# xmega-128a4u-switch.net
KiCad netlist of a schematic drawn in EAGLE
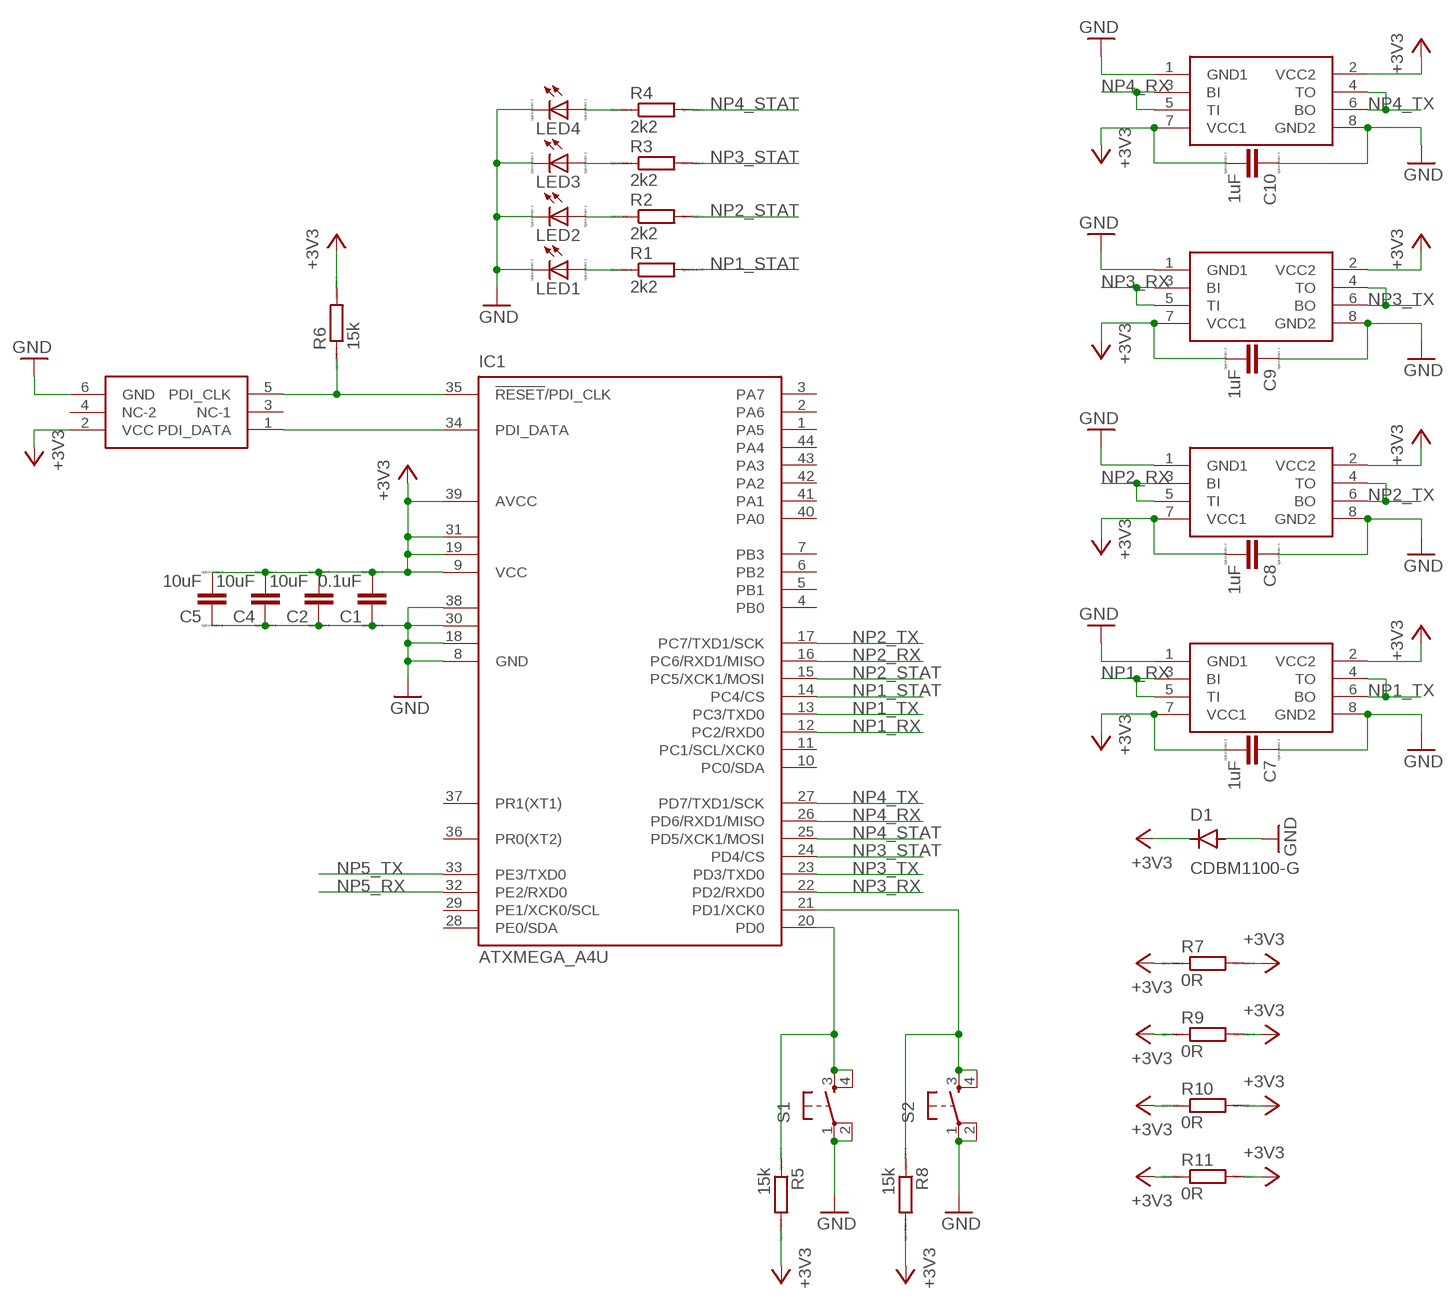
[diagram p0: schematic, sheet 1]

(export (version "E")
  (design (tool "Eeschema 10.0.6"))
  (components
    (comp (ref "C1")
      (value "0.1uF")
      (footprint "eagle-import:C0805")
      (libsource (lib "eagle-import") (part "C"))
    )
    (comp (ref "C2")
      (value "10uF")
      (footprint "eagle-import:C1206")
      (libsource (lib "eagle-import") (part "CC1206"))
    )
    (comp (ref "C4")
      (value "10uF")
      (footprint "eagle-import:C1206")
      (libsource (lib "eagle-import") (part "CC1206"))
    )
    (comp (ref "C5")
      (value "10uF")
      (footprint "eagle-import:C1206")
      (libsource (lib "eagle-import") (part "CC1206"))
    )
    (comp (ref "C7")
      (value "1uF")
      (footprint "eagle-import:C0805")
      (libsource (lib "eagle-import") (part "C"))
    )
    (comp (ref "C8")
      (value "1uF")
      (footprint "eagle-import:C0805")
      (libsource (lib "eagle-import") (part "C"))
    )
    (comp (ref "C9")
      (value "1uF")
      (footprint "eagle-import:C0805")
      (libsource (lib "eagle-import") (part "C"))
    )
    (comp (ref "C10")
      (value "1uF")
      (footprint "eagle-import:C0805")
      (libsource (lib "eagle-import") (part "C"))
    )
    (comp (ref "D1")
      (value "CDBM1100-G")
      (footprint "eagle-import:MINI-SMA")
      (libsource (lib "eagle-import") (part "CDBM1100-G"))
    )
    (comp (ref "IC1")
      (value "ATXMEGA_A4U")
      (footprint "eagle-import:TQFP44-13THIN")
      (libsource (lib "eagle-import") (part "ATXMEGA_A4U"))
    )
    (comp (ref "LED1")
      (value "LED_E")
      (footprint "eagle-import:LED_1206")
      (libsource (lib "eagle-import") (part "LED_E"))
    )
    (comp (ref "LED2")
      (value "LED_E")
      (footprint "eagle-import:LED_1206")
      (libsource (lib "eagle-import") (part "LED_E"))
    )
    (comp (ref "LED3")
      (value "LED_E")
      (footprint "eagle-import:LED_1206")
      (libsource (lib "eagle-import") (part "LED_E"))
    )
    (comp (ref "LED4")
      (value "LED_E")
      (footprint "eagle-import:LED_1206")
      (libsource (lib "eagle-import") (part "LED_E"))
    )
    (comp (ref "R1")
      (value "2k2")
      (footprint "eagle-import:R1206")
      (libsource (lib "eagle-import") (part "RR1206"))
    )
    (comp (ref "R2")
      (value "2k2")
      (footprint "eagle-import:R1206")
      (libsource (lib "eagle-import") (part "RR1206"))
    )
    (comp (ref "R3")
      (value "2k2")
      (footprint "eagle-import:R1206")
      (libsource (lib "eagle-import") (part "RR1206"))
    )
    (comp (ref "R4")
      (value "2k2")
      (footprint "eagle-import:R1206")
      (libsource (lib "eagle-import") (part "RR1206"))
    )
    (comp (ref "R5")
      (value "15k")
      (footprint "eagle-import:R0805")
      (libsource (lib "eagle-import") (part "R"))
    )
    (comp (ref "R6")
      (value "15k")
      (footprint "eagle-import:R0805")
      (libsource (lib "eagle-import") (part "R"))
    )
    (comp (ref "R7")
      (value "0R")
      (footprint "eagle-import:R1206")
      (libsource (lib "eagle-import") (part "RR1206"))
    )
    (comp (ref "R8")
      (value "15k")
      (footprint "eagle-import:R0805")
      (libsource (lib "eagle-import") (part "R"))
    )
    (comp (ref "R9")
      (value "0R")
      (footprint "eagle-import:R1206")
      (libsource (lib "eagle-import") (part "RR1206"))
    )
    (comp (ref "R10")
      (value "0R")
      (footprint "eagle-import:R1206")
      (libsource (lib "eagle-import") (part "RR1206"))
    )
    (comp (ref "R11")
      (value "0R")
      (footprint "eagle-import:R1206")
      (libsource (lib "eagle-import") (part "RR1206"))
    )
    (comp (ref "S1")
      (value "6MM_SWITCH6MM_SWITCH")
      (footprint "eagle-import:6MM_SWITCH")
      (libsource (lib "eagle-import") (part "6MM_SWITCH6MM_SWITCH"))
    )
    (comp (ref "S2")
      (value "6MM_SWITCH6MM_SWITCH")
      (footprint "eagle-import:6MM_SWITCH")
      (libsource (lib "eagle-import") (part "6MM_SWITCH6MM_SWITCH"))
    )
    (comp (ref "U$3")
      (value "NETPORT_IDC_FULLFLIP")
      (footprint "eagle-import:2X04SMD")
      (libsource (lib "eagle-import") (part "NETPORT_IDC_FULLFLIP"))
    )
    (comp (ref "U$4")
      (value "NETPORT_IDC_FULLFLIP")
      (footprint "eagle-import:2X04SMD")
      (libsource (lib "eagle-import") (part "NETPORT_IDC_FULLFLIP"))
    )
    (comp (ref "U$5")
      (value "NETPORT_IDC_FULLFLIP")
      (footprint "eagle-import:2X04SMD")
      (libsource (lib "eagle-import") (part "NETPORT_IDC_FULLFLIP"))
    )
    (comp (ref "U$6")
      (value "NETPORT_IDC_FULLFLIP")
      (footprint "eagle-import:2X04SMD")
      (libsource (lib "eagle-import") (part "NETPORT_IDC_FULLFLIP"))
    )
    (comp (ref "U$7")
      (value "PDI")
      (footprint "eagle-import:2X03SMD")
      (libsource (lib "eagle-import") (part "PDI"))
    )
  )
  (nets
    (net (code "1") (name "+3V3") (class "Default")
      (node (ref "C1") (pin "2") (pinfunction "2_2") (pintype "passive"))
      (node (ref "C10") (pin "2") (pinfunction "2_2") (pintype "passive"))
      (node (ref "C2") (pin "2") (pinfunction "2_2") (pintype "passive"))
      (node (ref "C4") (pin "2") (pinfunction "2_2") (pintype "passive"))
      (node (ref "C5") (pin "2") (pinfunction "2_2") (pintype "passive"))
      (node (ref "C7") (pin "2") (pinfunction "2_2") (pintype "passive"))
      (node (ref "C8") (pin "2") (pinfunction "2_2") (pintype "passive"))
      (node (ref "C9") (pin "2") (pinfunction "2_2") (pintype "passive"))
      (node (ref "D1") (pin "KATHODE") (pinfunction "KATHODE_KATHODE") (pintype "bidirectional"))
      (node (ref "IC1") (pin "19") (pinfunction "VCC1_19") (pintype "power_in"))
      (node (ref "IC1") (pin "31") (pinfunction "VCC2_31") (pintype "power_in"))
      (node (ref "IC1") (pin "39") (pinfunction "AVCC_39") (pintype "power_in"))
      (node (ref "IC1") (pin "9") (pinfunction "VCC_9") (pintype "power_in"))
      (node (ref "R10") (pin "1") (pinfunction "1_1") (pintype "passive"))
      (node (ref "R10") (pin "2") (pinfunction "2_2") (pintype "passive"))
      (node (ref "R11") (pin "1") (pinfunction "1_1") (pintype "passive"))
      (node (ref "R11") (pin "2") (pinfunction "2_2") (pintype "passive"))
      (node (ref "R5") (pin "2") (pinfunction "2_2") (pintype "passive"))
      (node (ref "R6") (pin "2") (pinfunction "2_2") (pintype "passive"))
      (node (ref "R7") (pin "1") (pinfunction "1_1") (pintype "passive"))
      (node (ref "R7") (pin "2") (pinfunction "2_2") (pintype "passive"))
      (node (ref "R8") (pin "2") (pinfunction "2_2") (pintype "passive"))
      (node (ref "R9") (pin "1") (pinfunction "1_1") (pintype "passive"))
      (node (ref "R9") (pin "2") (pinfunction "2_2") (pintype "passive"))
      (node (ref "U$3") (pin "2") (pinfunction "VCC2_2") (pintype "bidirectional"))
      (node (ref "U$3") (pin "7") (pinfunction "VCC1_7") (pintype "bidirectional"))
      (node (ref "U$4") (pin "2") (pinfunction "VCC2_2") (pintype "bidirectional"))
      (node (ref "U$4") (pin "7") (pinfunction "VCC1_7") (pintype "bidirectional"))
      (node (ref "U$5") (pin "2") (pinfunction "VCC2_2") (pintype "bidirectional"))
      (node (ref "U$5") (pin "7") (pinfunction "VCC1_7") (pintype "bidirectional"))
      (node (ref "U$6") (pin "2") (pinfunction "VCC2_2") (pintype "bidirectional"))
      (node (ref "U$6") (pin "7") (pinfunction "VCC1_7") (pintype "bidirectional"))
      (node (ref "U$7") (pin "2") (pinfunction "VCC_2") (pintype "bidirectional"))
    )
    (net (code "2") (name "/NP1_RX") (class "Default")
      (node (ref "IC1") (pin "12") (pinfunction "PC2/RXD0_12") (pintype "bidirectional"))
      (node (ref "U$3") (pin "3") (pinfunction "BI_3") (pintype "bidirectional"))
      (node (ref "U$3") (pin "5") (pinfunction "TI_5") (pintype "bidirectional"))
    )
    (net (code "3") (name "/NP1_STAT") (class "Default")
      (node (ref "IC1") (pin "14") (pinfunction "PC4/CS_14") (pintype "bidirectional"))
      (node (ref "R1") (pin "2") (pinfunction "2_2") (pintype "passive"))
    )
    (net (code "4") (name "/NP1_TX") (class "Default")
      (node (ref "IC1") (pin "13") (pinfunction "PC3/TXD0_13") (pintype "bidirectional"))
      (node (ref "U$3") (pin "4") (pinfunction "TO_4") (pintype "bidirectional"))
      (node (ref "U$3") (pin "6") (pinfunction "BO_6") (pintype "bidirectional"))
    )
    (net (code "5") (name "/NP2_RX") (class "Default")
      (node (ref "IC1") (pin "16") (pinfunction "PC6/RXD1/MISO_16") (pintype "bidirectional"))
      (node (ref "U$4") (pin "3") (pinfunction "BI_3") (pintype "bidirectional"))
      (node (ref "U$4") (pin "5") (pinfunction "TI_5") (pintype "bidirectional"))
    )
    (net (code "6") (name "/NP2_STAT") (class "Default")
      (node (ref "IC1") (pin "15") (pinfunction "PC5/XCK1/MOSI_15") (pintype "bidirectional"))
      (node (ref "R2") (pin "2") (pinfunction "2_2") (pintype "passive"))
    )
    (net (code "7") (name "/NP2_TX") (class "Default")
      (node (ref "IC1") (pin "17") (pinfunction "PC7/TXD1/SCK_17") (pintype "bidirectional"))
      (node (ref "U$4") (pin "4") (pinfunction "TO_4") (pintype "bidirectional"))
      (node (ref "U$4") (pin "6") (pinfunction "BO_6") (pintype "bidirectional"))
    )
    (net (code "8") (name "/NP3_RX") (class "Default")
      (node (ref "IC1") (pin "22") (pinfunction "PD2/RXD0_22") (pintype "bidirectional"))
      (node (ref "U$5") (pin "3") (pinfunction "BI_3") (pintype "bidirectional"))
      (node (ref "U$5") (pin "5") (pinfunction "TI_5") (pintype "bidirectional"))
    )
    (net (code "9") (name "/NP3_STAT") (class "Default")
      (node (ref "IC1") (pin "24") (pinfunction "PD4/CS_24") (pintype "bidirectional"))
      (node (ref "R3") (pin "2") (pinfunction "2_2") (pintype "passive"))
    )
    (net (code "10") (name "/NP3_TX") (class "Default")
      (node (ref "IC1") (pin "23") (pinfunction "PD3/TXD0_23") (pintype "bidirectional"))
      (node (ref "U$5") (pin "4") (pinfunction "TO_4") (pintype "bidirectional"))
      (node (ref "U$5") (pin "6") (pinfunction "BO_6") (pintype "bidirectional"))
    )
    (net (code "11") (name "/NP4_RX") (class "Default")
      (node (ref "IC1") (pin "26") (pinfunction "PD6/RXD1/MISO_26") (pintype "bidirectional"))
      (node (ref "U$6") (pin "3") (pinfunction "BI_3") (pintype "bidirectional"))
      (node (ref "U$6") (pin "5") (pinfunction "TI_5") (pintype "bidirectional"))
    )
    (net (code "12") (name "/NP4_STAT") (class "Default")
      (node (ref "IC1") (pin "25") (pinfunction "PD5/XCK1/MOSI_25") (pintype "bidirectional"))
      (node (ref "R4") (pin "2") (pinfunction "2_2") (pintype "passive"))
    )
    (net (code "13") (name "/NP4_TX") (class "Default")
      (node (ref "IC1") (pin "27") (pinfunction "PD7/TXD1/SCK_27") (pintype "bidirectional"))
      (node (ref "U$6") (pin "4") (pinfunction "TO_4") (pintype "bidirectional"))
      (node (ref "U$6") (pin "6") (pinfunction "BO_6") (pintype "bidirectional"))
    )
    (net (code "14") (name "/NP5_RX") (class "Default")
      (node (ref "IC1") (pin "32") (pinfunction "PE2/RXD0_32") (pintype "bidirectional"))
    )
    (net (code "15") (name "/NP5_TX") (class "Default")
      (node (ref "IC1") (pin "33") (pinfunction "PE3/TXD0_33") (pintype "bidirectional"))
    )
    (net (code "16") (name "GND") (class "Default")
      (node (ref "C1") (pin "1") (pinfunction "1_1") (pintype "passive"))
      (node (ref "C10") (pin "1") (pinfunction "1_1") (pintype "passive"))
      (node (ref "C2") (pin "1") (pinfunction "1_1") (pintype "passive"))
      (node (ref "C4") (pin "1") (pinfunction "1_1") (pintype "passive"))
      (node (ref "C5") (pin "1") (pinfunction "1_1") (pintype "passive"))
      (node (ref "C7") (pin "1") (pinfunction "1_1") (pintype "passive"))
      (node (ref "C8") (pin "1") (pinfunction "1_1") (pintype "passive"))
      (node (ref "C9") (pin "1") (pinfunction "1_1") (pintype "passive"))
      (node (ref "D1") (pin "ANODE") (pinfunction "ANODE_ANODE") (pintype "bidirectional"))
      (node (ref "IC1") (pin "18") (pinfunction "GND1_18") (pintype "power_in"))
      (node (ref "IC1") (pin "30") (pinfunction "GND2_30") (pintype "power_in"))
      (node (ref "IC1") (pin "38") (pinfunction "GND3_38") (pintype "power_in"))
      (node (ref "IC1") (pin "8") (pinfunction "GND_8") (pintype "power_in"))
      (node (ref "LED1") (pin "C") (pinfunction "C_C") (pintype "passive"))
      (node (ref "LED2") (pin "C") (pinfunction "C_C") (pintype "passive"))
      (node (ref "LED3") (pin "C") (pinfunction "C_C") (pintype "passive"))
      (node (ref "LED4") (pin "C") (pinfunction "C_C") (pintype "passive"))
      (node (ref "S1") (pin "1") (pinfunction "P_1") (pintype "passive"))
      (node (ref "S1") (pin "2") (pinfunction "P1_2") (pintype "passive"))
      (node (ref "S2") (pin "1") (pinfunction "P_1") (pintype "passive"))
      (node (ref "S2") (pin "2") (pinfunction "P1_2") (pintype "passive"))
      (node (ref "U$3") (pin "1") (pinfunction "GND1_1") (pintype "bidirectional"))
      (node (ref "U$3") (pin "8") (pinfunction "GND2_8") (pintype "bidirectional"))
      (node (ref "U$4") (pin "1") (pinfunction "GND1_1") (pintype "bidirectional"))
      (node (ref "U$4") (pin "8") (pinfunction "GND2_8") (pintype "bidirectional"))
      (node (ref "U$5") (pin "1") (pinfunction "GND1_1") (pintype "bidirectional"))
      (node (ref "U$5") (pin "8") (pinfunction "GND2_8") (pintype "bidirectional"))
      (node (ref "U$6") (pin "1") (pinfunction "GND1_1") (pintype "bidirectional"))
      (node (ref "U$6") (pin "8") (pinfunction "GND2_8") (pintype "bidirectional"))
      (node (ref "U$7") (pin "6") (pinfunction "GND_6") (pintype "bidirectional"))
    )
    (net (code "17") (name "Net-(IC1-PD0)") (class "Default")
      (node (ref "IC1") (pin "20") (pinfunction "PD0_20") (pintype "bidirectional"))
      (node (ref "R5") (pin "1") (pinfunction "1_1") (pintype "passive"))
      (node (ref "S1") (pin "3") (pinfunction "S_3") (pintype "passive"))
      (node (ref "S1") (pin "4") (pinfunction "S1_4") (pintype "passive"))
    )
    (net (code "18") (name "Net-(IC1-PD1{slash}XCK0)") (class "Default")
      (node (ref "IC1") (pin "21") (pinfunction "PD1/XCK0_21") (pintype "bidirectional"))
      (node (ref "R8") (pin "1") (pinfunction "1_1") (pintype "passive"))
      (node (ref "S2") (pin "3") (pinfunction "S_3") (pintype "passive"))
      (node (ref "S2") (pin "4") (pinfunction "S1_4") (pintype "passive"))
    )
    (net (code "19") (name "Net-(IC1-PDI_DATA)") (class "Default")
      (node (ref "IC1") (pin "34") (pinfunction "PDI_DATA_34") (pintype "bidirectional"))
      (node (ref "U$7") (pin "1") (pinfunction "PDI_DATA_1") (pintype "bidirectional"))
    )
    (net (code "20") (name "Net-(IC1-~{RESET}{slash}PDI_CLK)") (class "Default")
      (node (ref "IC1") (pin "35") (pinfunction "~{RESET}/PDI_CLK_35") (pintype "bidirectional"))
      (node (ref "R6") (pin "1") (pinfunction "1_1") (pintype "passive"))
      (node (ref "U$7") (pin "5") (pinfunction "PDI_CLK_5") (pintype "bidirectional"))
    )
    (net (code "21") (name "Net-(LED1-PadA)") (class "Default")
      (node (ref "LED1") (pin "A") (pinfunction "A_A") (pintype "passive"))
      (node (ref "R1") (pin "1") (pinfunction "1_1") (pintype "passive"))
    )
    (net (code "22") (name "Net-(LED2-PadA)") (class "Default")
      (node (ref "LED2") (pin "A") (pinfunction "A_A") (pintype "passive"))
      (node (ref "R2") (pin "1") (pinfunction "1_1") (pintype "passive"))
    )
    (net (code "23") (name "Net-(LED3-PadA)") (class "Default")
      (node (ref "LED3") (pin "A") (pinfunction "A_A") (pintype "passive"))
      (node (ref "R3") (pin "1") (pinfunction "1_1") (pintype "passive"))
    )
    (net (code "24") (name "Net-(LED4-PadA)") (class "Default")
      (node (ref "LED4") (pin "A") (pinfunction "A_A") (pintype "passive"))
      (node (ref "R4") (pin "1") (pinfunction "1_1") (pintype "passive"))
    )
    (net (code "25") (name "unconnected-(IC1-PA0-Pad40)") (class "Default")
      (node (ref "IC1") (pin "40") (pinfunction "PA0_40") (pintype "bidirectional"))
    )
    (net (code "26") (name "unconnected-(IC1-PA1-Pad41)") (class "Default")
      (node (ref "IC1") (pin "41") (pinfunction "PA1_41") (pintype "bidirectional"))
    )
    (net (code "27") (name "unconnected-(IC1-PA2-Pad42)") (class "Default")
      (node (ref "IC1") (pin "42") (pinfunction "PA2_42") (pintype "bidirectional"))
    )
    (net (code "28") (name "unconnected-(IC1-PA3-Pad43)") (class "Default")
      (node (ref "IC1") (pin "43") (pinfunction "PA3_43") (pintype "bidirectional"))
    )
    (net (code "29") (name "unconnected-(IC1-PA4-Pad44)") (class "Default")
      (node (ref "IC1") (pin "44") (pinfunction "PA4_44") (pintype "bidirectional"))
    )
    (net (code "30") (name "unconnected-(IC1-PA5-Pad1)") (class "Default")
      (node (ref "IC1") (pin "1") (pinfunction "PA5_1") (pintype "bidirectional"))
    )
    (net (code "31") (name "unconnected-(IC1-PA6-Pad2)") (class "Default")
      (node (ref "IC1") (pin "2") (pinfunction "PA6_2") (pintype "bidirectional"))
    )
    (net (code "32") (name "unconnected-(IC1-PA7-Pad3)") (class "Default")
      (node (ref "IC1") (pin "3") (pinfunction "PA7_3") (pintype "bidirectional"))
    )
    (net (code "33") (name "unconnected-(IC1-PB0-Pad4)") (class "Default")
      (node (ref "IC1") (pin "4") (pinfunction "PB0_4") (pintype "bidirectional"))
    )
    (net (code "34") (name "unconnected-(IC1-PB1-Pad5)") (class "Default")
      (node (ref "IC1") (pin "5") (pinfunction "PB1_5") (pintype "bidirectional"))
    )
    (net (code "35") (name "unconnected-(IC1-PB2-Pad6)") (class "Default")
      (node (ref "IC1") (pin "6") (pinfunction "PB2_6") (pintype "bidirectional"))
    )
    (net (code "36") (name "unconnected-(IC1-PB3-Pad7)") (class "Default")
      (node (ref "IC1") (pin "7") (pinfunction "PB3_7") (pintype "bidirectional"))
    )
    (net (code "37") (name "unconnected-(IC1-PC0{slash}SDA-Pad10)") (class "Default")
      (node (ref "IC1") (pin "10") (pinfunction "PC0/SDA_10") (pintype "bidirectional"))
    )
    (net (code "38") (name "unconnected-(IC1-PC1{slash}SCL{slash}XCK0-Pad11)") (class "Default")
      (node (ref "IC1") (pin "11") (pinfunction "PC1/SCL/XCK0_11") (pintype "bidirectional"))
    )
    (net (code "39") (name "unconnected-(IC1-PE0{slash}SDA-Pad28)") (class "Default")
      (node (ref "IC1") (pin "28") (pinfunction "PE0/SDA_28") (pintype "bidirectional"))
    )
    (net (code "40") (name "unconnected-(IC1-PE1{slash}XCK0{slash}SCL-Pad29)") (class "Default")
      (node (ref "IC1") (pin "29") (pinfunction "PE1/XCK0/SCL_29") (pintype "bidirectional"))
    )
    (net (code "41") (name "unconnected-(IC1-PR0(XT2)-Pad36)") (class "Default")
      (node (ref "IC1") (pin "36") (pinfunction "PR0(XT2)_36") (pintype "bidirectional"))
    )
    (net (code "42") (name "unconnected-(IC1-PR1(XT1)-Pad37)") (class "Default")
      (node (ref "IC1") (pin "37") (pinfunction "PR1(XT1)_37") (pintype "bidirectional"))
    )
    (net (code "43") (name "unconnected-(U$7-NC-1-Pad3)") (class "Default")
      (node (ref "U$7") (pin "3") (pinfunction "NC-1_3") (pintype "bidirectional"))
    )
    (net (code "44") (name "unconnected-(U$7-NC-2-Pad4)") (class "Default")
      (node (ref "U$7") (pin "4") (pinfunction "NC-2_4") (pintype "bidirectional"))
    )
  )
)
